# arduino_Uno_Rev3-02-TH-Mod-berred180302.net
KiCad netlist of a schematic drawn in EAGLE
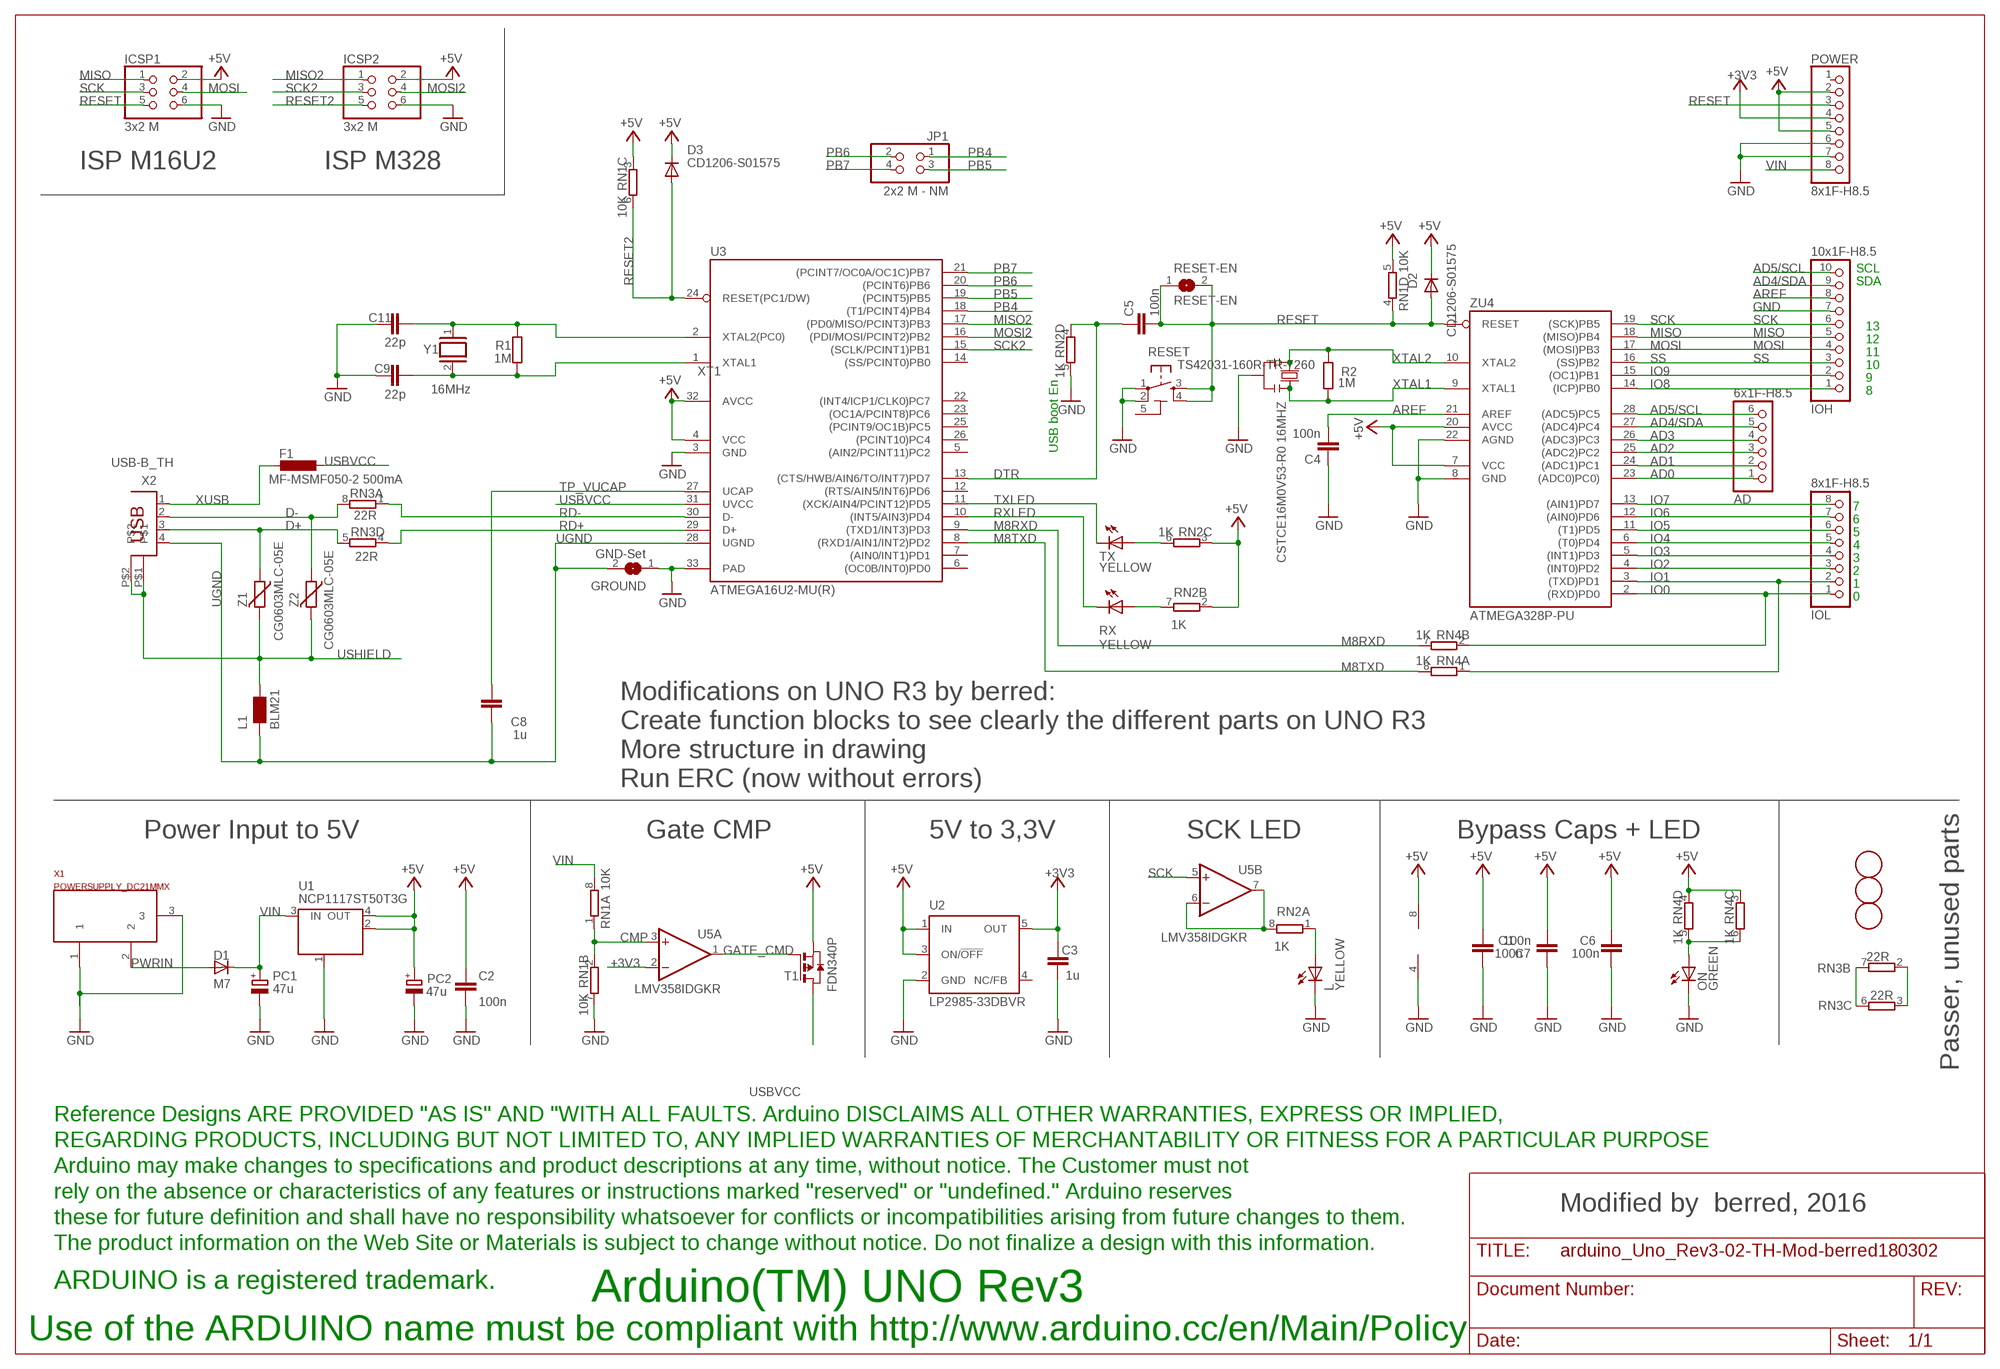
[diagram p0: schematic, sheet 1]

(export (version "E")
  (design (tool "Eeschema 10.0.6"))
  (components
    (comp (ref "AD")
      (value "6x1F-H8.5")
      (footprint "eagle-import:1X06")
      (libsource (lib "eagle-import") (part "PINHD-1X6"))
    )
    (comp (ref "C1")
      (value "100n")
      (footprint "eagle-import:C0603-ROUND")
      (libsource (lib "eagle-import") (part "C-EU0603-RND"))
    )
    (comp (ref "C2")
      (value "100n")
      (footprint "eagle-import:C0603-ROUND")
      (libsource (lib "eagle-import") (part "C-EU0603-RND"))
    )
    (comp (ref "C3")
      (value "1u")
      (footprint "eagle-import:C0603-ROUND")
      (libsource (lib "eagle-import") (part "C-EU0603-RND"))
    )
    (comp (ref "C4")
      (value "100n")
      (footprint "eagle-import:C0603-ROUND")
      (libsource (lib "eagle-import") (part "C-EU0603-RND"))
    )
    (comp (ref "C5")
      (value "100n")
      (footprint "eagle-import:C0603-ROUND")
      (libsource (lib "eagle-import") (part "C-EU0603-RND"))
    )
    (comp (ref "C6")
      (value "100n")
      (footprint "eagle-import:C0603-ROUND")
      (libsource (lib "eagle-import") (part "C-EU0603-RND"))
    )
    (comp (ref "C7")
      (value "100n")
      (footprint "eagle-import:C0603-ROUND")
      (libsource (lib "eagle-import") (part "C-EU0603-RND"))
    )
    (comp (ref "C8")
      (value "1u")
      (footprint "eagle-import:C0603-ROUND")
      (libsource (lib "eagle-import") (part "C-EU0603-RND"))
    )
    (comp (ref "C9")
      (value "22p")
      (footprint "eagle-import:C0603-ROUND")
      (libsource (lib "eagle-import") (part "C-EU0603-RND"))
    )
    (comp (ref "C11")
      (value "22p")
      (footprint "eagle-import:C0603-ROUND")
      (libsource (lib "eagle-import") (part "C-EU0603-RND"))
    )
    (comp (ref "D1")
      (value "M7")
      (footprint "eagle-import:SMB")
      (libsource (lib "eagle-import") (part "DIODE-SMB"))
    )
    (comp (ref "D2")
      (value "CD1206-S01575")
      (footprint "eagle-import:MINIMELF")
      (libsource (lib "eagle-import") (part "DIODE-MINIMELF"))
    )
    (comp (ref "D3")
      (value "CD1206-S01575")
      (footprint "eagle-import:MINIMELF")
      (libsource (lib "eagle-import") (part "DIODE-MINIMELF"))
    )
    (comp (ref "F1")
      (value "MF-MSMF050-2 500mA")
      (footprint "eagle-import:L1812")
      (libsource (lib "eagle-import") (part "L-EUL1812"))
    )
    (comp (ref "FD1")
      (value "FIDUCIALMOUNT")
      (footprint "eagle-import:FIDUCIA-MOUNT")
      (libsource (lib "eagle-import") (part "FIDUCIALMOUNT"))
    )
    (comp (ref "FD2")
      (value "FIDUCIALMOUNT")
      (footprint "eagle-import:FIDUCIA-MOUNT")
      (libsource (lib "eagle-import") (part "FIDUCIALMOUNT"))
    )
    (comp (ref "FD3")
      (value "FIDUCIALMOUNT")
      (footprint "eagle-import:FIDUCIA-MOUNT")
      (libsource (lib "eagle-import") (part "FIDUCIALMOUNT"))
    )
    (comp (ref "GROUND")
      (value "GND-Set")
      (footprint "eagle-import:SJ")
      (libsource (lib "eagle-import") (part "SJ"))
    )
    (comp (ref "ICSP1")
      (value "3x2 M")
      (footprint "eagle-import:2X03")
      (libsource (lib "eagle-import") (part "PINHD-2X3"))
    )
    (comp (ref "ICSP2")
      (value "3x2 M")
      (footprint "eagle-import:2X03")
      (libsource (lib "eagle-import") (part "PINHD-2X3"))
    )
    (comp (ref "IOH")
      (value "10x1F-H8.5")
      (footprint "eagle-import:1X10")
      (libsource (lib "eagle-import") (part "PINHD-1X10_ARD"))
    )
    (comp (ref "IOL")
      (value "8x1F-H8.5")
      (footprint "eagle-import:1X08")
      (libsource (lib "eagle-import") (part "PINHD-1X8"))
    )
    (comp (ref "JP1")
      (value "2x2 M - NM")
      (footprint "eagle-import:2X02")
      (libsource (lib "eagle-import") (part "PINHD-2X2"))
    )
    (comp (ref "L")
      (value "YELLOW")
      (footprint "eagle-import:CHIP-LED0805")
      (libsource (lib "eagle-import") (part "LEDCHIP-LED0805"))
    )
    (comp (ref "L1")
      (value "BLM21")
      (footprint "eagle-import:0805")
      (libsource (lib "eagle-import") (part "WE-CBF_0805"))
    )
    (comp (ref "ON")
      (value "GREEN")
      (footprint "eagle-import:CHIP-LED0805")
      (libsource (lib "eagle-import") (part "LEDCHIP-LED0805"))
    )
    (comp (ref "PC1")
      (value "47u")
      (footprint "eagle-import:PANASONIC_D")
      (libsource (lib "eagle-import") (part "CPOL-EUD"))
    )
    (comp (ref "PC2")
      (value "47u")
      (footprint "eagle-import:PANASONIC_D")
      (libsource (lib "eagle-import") (part "CPOL-EUD"))
    )
    (comp (ref "POWER")
      (value "8x1F-H8.5")
      (footprint "eagle-import:1X08")
      (libsource (lib "eagle-import") (part "PINHD-1X8"))
    )
    (comp (ref "R1")
      (value "1M")
      (footprint "eagle-import:R0603-ROUND")
      (libsource (lib "eagle-import") (part "R-EU_R0603"))
    )
    (comp (ref "R2")
      (value "1M")
      (footprint "eagle-import:R0603-ROUND")
      (libsource (lib "eagle-import") (part "R-EU_R0603"))
    )
    (comp (ref "RESET")
      (value "TS42031-160R-TR-7260")
      (footprint "eagle-import:TS42")
      (libsource (lib "eagle-import") (part "TS42"))
    )
    (comp (ref "RESET-EN")
      (value "RESET-EN")
      (footprint "eagle-import:SJ")
      (libsource (lib "eagle-import") (part "SJ"))
    )
    (comp (ref "RN1")
      (value "10K")
      (footprint "eagle-import:CAY16")
      (libsource (lib "eagle-import") (part "4R-NCAY16"))
    )
    (comp (ref "RN2")
      (value "1K")
      (footprint "eagle-import:CAY16")
      (libsource (lib "eagle-import") (part "4R-NCAY16"))
    )
    (comp (ref "RN3")
      (value "22R")
      (footprint "eagle-import:CAY16")
      (libsource (lib "eagle-import") (part "4R-NCAY16"))
    )
    (comp (ref "RN4")
      (value "1K")
      (footprint "eagle-import:CAY16")
      (libsource (lib "eagle-import") (part "4R-NCAY16"))
    )
    (comp (ref "RX")
      (value "YELLOW")
      (footprint "eagle-import:CHIP-LED0805")
      (libsource (lib "eagle-import") (part "LEDCHIP-LED0805"))
    )
    (comp (ref "T1")
      (value "FDN340P")
      (footprint "eagle-import:SOT-23")
      (libsource (lib "eagle-import") (part "PMOSSOT23"))
    )
    (comp (ref "TX")
      (value "YELLOW")
      (footprint "eagle-import:CHIP-LED0805")
      (libsource (lib "eagle-import") (part "LEDCHIP-LED0805"))
    )
    (comp (ref "U$1")
      (value "DISCLAIMER")
      (footprint "eagle-import:DISCLAIMER")
      (libsource (lib "eagle-import") (part "DISCLAIMER"))
    )
    (comp (ref "U1")
      (value "NCP1117ST50T3G")
      (footprint "eagle-import:SOT223")
      (libsource (lib "eagle-import") (part "MC33269ST-3.3T3"))
    )
    (comp (ref "U2")
      (value "LP2985-33DBVR")
      (footprint "eagle-import:SOT23-DBV")
      (libsource (lib "eagle-import") (part "LP2985-XXDBVR33"))
    )
    (comp (ref "U3")
      (value "ATMEGA16U2-MU(R)")
      (footprint "eagle-import:MLF32")
      (libsource (lib "eagle-import") (part "ATMEGA16U2-MU"))
    )
    (comp (ref "U5")
      (value "LMV358IDGKR")
      (footprint "eagle-import:MSOP08")
      (libsource (lib "eagle-import") (part "LMV358?MMX"))
    )
    (comp (ref "X1")
      (value "POWERSUPPLY_DC21MMX")
      (footprint "eagle-import:POWERSUPPLY_DC-21MM")
      (libsource (lib "eagle-import") (part "POWERSUPPLY_DC21MMX"))
    )
    (comp (ref "X2")
      (value "USB-B_TH")
      (footprint "eagle-import:PN61729")
      (libsource (lib "eagle-import") (part "PN61729"))
    )
    (comp (ref "Y1")
      (value "16MHz")
      (footprint "eagle-import:QS")
      (libsource (lib "eagle-import") (part "XTAL/S"))
    )
    (comp (ref "Y2")
      (value "CSTCE16M0V53-R0 16MHZ")
      (footprint "eagle-import:RESONATOR")
      (libsource (lib "eagle-import") (part "RESONATORMU"))
    )
    (comp (ref "Z1")
      (value "CG0603MLC-05E")
      (footprint "eagle-import:CT_CN0603")
      (libsource (lib "eagle-import") (part "VARISTORCN0603"))
    )
    (comp (ref "Z2")
      (value "CG0603MLC-05E")
      (footprint "eagle-import:CT_CN0603")
      (libsource (lib "eagle-import") (part "VARISTORCN0603"))
    )
    (comp (ref "ZU4")
      (value "ATMEGA328P-PU")
      (footprint "eagle-import:DIL28-3")
      (libsource (lib "eagle-import") (part "ATMEGA328P-PU"))
    )
  )
  (nets
    (net (code "1") (name "+3V3") (class "Default")
      (node (ref "C3") (pin "2") (pinfunction "2_2") (pintype "passive"))
      (node (ref "POWER") (pin "4") (pinfunction "4_4") (pintype "passive"))
      (node (ref "U2") (pin "5") (pinfunction "OUT_5") (pintype "passive"))
      (node (ref "U5") (pin "2") (pinfunction "-IN_2") (pintype "input"))
    )
    (net (code "2") (name "+5V") (class "Default")
      (node (ref "C1") (pin "2") (pinfunction "2_2") (pintype "passive"))
      (node (ref "C2") (pin "2") (pinfunction "2_2") (pintype "passive"))
      (node (ref "C6") (pin "2") (pinfunction "2_2") (pintype "passive"))
      (node (ref "C7") (pin "1") (pinfunction "1_1") (pintype "passive"))
      (node (ref "D2") (pin "C") (pinfunction "C_C") (pintype "passive"))
      (node (ref "D3") (pin "C") (pinfunction "C_C") (pintype "passive"))
      (node (ref "ICSP1") (pin "2") (pinfunction "2_2") (pintype "passive"))
      (node (ref "ICSP2") (pin "2") (pinfunction "2_2") (pintype "passive"))
      (node (ref "PC2") (pin "+") (pinfunction "+_+") (pintype "passive"))
      (node (ref "POWER") (pin "2") (pinfunction "2_2") (pintype "passive"))
      (node (ref "POWER") (pin "5") (pinfunction "5_5") (pintype "passive"))
      (node (ref "RN1") (pin "3") (pinfunction "1_3") (pintype "passive"))
      (node (ref "RN1") (pin "5") (pinfunction "2_5") (pintype "passive"))
      (node (ref "RN2") (pin "2") (pinfunction "1_2") (pintype "passive"))
      (node (ref "RN2") (pin "3") (pinfunction "1_3") (pintype "passive"))
      (node (ref "RN4") (pin "3") (pinfunction "1_3") (pintype "passive"))
      (node (ref "RN4") (pin "4") (pinfunction "1_4") (pintype "passive"))
      (node (ref "T1") (pin "2") (pinfunction "S_2") (pintype "passive"))
      (node (ref "U1") (pin "2") (pinfunction "OUT_2") (pintype "passive"))
      (node (ref "U1") (pin "4") (pinfunction "OUT_4") (pintype "passive"))
      (node (ref "U2") (pin "1") (pinfunction "IN_1") (pintype "input"))
      (node (ref "U2") (pin "3") (pinfunction "ON/~{OFF}_3") (pintype "input"))
      (node (ref "U3") (pin "32") (pinfunction "AVCC_32") (pintype "power_in"))
      (node (ref "U3") (pin "4") (pinfunction "VCC_4") (pintype "power_in"))
      (node (ref "U5") (pin "8") (pinfunction "V+_8") (pintype "power_in"))
      (node (ref "ZU4") (pin "20") (pinfunction "AVCC_20") (pintype "power_in"))
      (node (ref "ZU4") (pin "7") (pinfunction "VCC_7") (pintype "power_in"))
    )
    (net (code "3") (name "/5-GND") (class "Default")
      (node (ref "RESET") (pin "5") (pinfunction "5-GND_5") (pintype "power_in"))
    )
    (net (code "4") (name "/AD0") (class "Default")
      (node (ref "AD") (pin "1") (pinfunction "1_1") (pintype "passive"))
      (node (ref "ZU4") (pin "23") (pinfunction "(ADC0)PC0)_23") (pintype "bidirectional"))
    )
    (net (code "5") (name "/AD1") (class "Default")
      (node (ref "AD") (pin "2") (pinfunction "2_2") (pintype "passive"))
      (node (ref "ZU4") (pin "24") (pinfunction "(ADC1)PC1_24") (pintype "bidirectional"))
    )
    (net (code "6") (name "/AD2") (class "Default")
      (node (ref "AD") (pin "3") (pinfunction "3_3") (pintype "passive"))
      (node (ref "ZU4") (pin "25") (pinfunction "(ADC2)PC2_25") (pintype "bidirectional"))
    )
    (net (code "7") (name "/AD3") (class "Default")
      (node (ref "AD") (pin "4") (pinfunction "4_4") (pintype "passive"))
      (node (ref "ZU4") (pin "26") (pinfunction "(ADC3)PC3_26") (pintype "bidirectional"))
    )
    (net (code "8") (name "/AD4{slash}SDA") (class "Default")
      (node (ref "AD") (pin "5") (pinfunction "5_5") (pintype "passive"))
      (node (ref "IOH") (pin "9") (pinfunction "9_9") (pintype "passive"))
      (node (ref "ZU4") (pin "27") (pinfunction "(ADC4)PC4_27") (pintype "bidirectional"))
    )
    (net (code "9") (name "/AD5{slash}SCL") (class "Default")
      (node (ref "AD") (pin "6") (pinfunction "6_6") (pintype "passive"))
      (node (ref "IOH") (pin "10") (pinfunction "10_10") (pintype "passive"))
      (node (ref "ZU4") (pin "28") (pinfunction "(ADC5)PC5_28") (pintype "bidirectional"))
    )
    (net (code "10") (name "/AREF") (class "Default")
      (node (ref "C4") (pin "2") (pinfunction "2_2") (pintype "passive"))
      (node (ref "IOH") (pin "8") (pinfunction "8_8") (pintype "passive"))
      (node (ref "ZU4") (pin "21") (pinfunction "AREF_21") (pintype "passive"))
    )
    (net (code "11") (name "/CMP") (class "Default")
      (node (ref "RN1") (pin "1") (pinfunction "1_1") (pintype "passive"))
      (node (ref "RN1") (pin "2") (pinfunction "1_2") (pintype "passive"))
      (node (ref "U5") (pin "3") (pinfunction "+IN_3") (pintype "input"))
    )
    (net (code "12") (name "/D+") (class "Default")
      (node (ref "RN3") (pin "5") (pinfunction "2_5") (pintype "passive"))
      (node (ref "X2") (pin "3") (pinfunction "3_3") (pintype "bidirectional"))
      (node (ref "Z1") (pin "1") (pinfunction "1_1") (pintype "passive"))
    )
    (net (code "13") (name "/D-") (class "Default")
      (node (ref "RN3") (pin "8") (pinfunction "2_8") (pintype "passive"))
      (node (ref "X2") (pin "2") (pinfunction "2_2") (pintype "bidirectional"))
      (node (ref "Z2") (pin "1") (pinfunction "1_1") (pintype "passive"))
    )
    (net (code "14") (name "/DTR") (class "Default")
      (node (ref "C5") (pin "1") (pinfunction "1_1") (pintype "passive"))
      (node (ref "RN2") (pin "4") (pinfunction "1_4") (pintype "passive"))
      (node (ref "U3") (pin "13") (pinfunction "(CTS/HWB/AIN6/TO/INT7)PD7_13") (pintype "bidirectional"))
    )
    (net (code "15") (name "/GATE_CMD") (class "Default")
      (node (ref "T1") (pin "3") (pinfunction "G_3") (pintype "passive"))
      (node (ref "U5") (pin "1") (pinfunction "OUT_1") (pintype "output"))
    )
    (net (code "16") (name "/IO0") (class "Default")
      (node (ref "IOL") (pin "1") (pinfunction "1_1") (pintype "passive"))
      (node (ref "RN4") (pin "2") (pinfunction "1_2") (pintype "passive"))
      (node (ref "ZU4") (pin "2") (pinfunction "(RXD)PD0_2") (pintype "bidirectional"))
    )
    (net (code "17") (name "/IO1") (class "Default")
      (node (ref "IOL") (pin "2") (pinfunction "2_2") (pintype "passive"))
      (node (ref "RN4") (pin "1") (pinfunction "1_1") (pintype "passive"))
      (node (ref "ZU4") (pin "3") (pinfunction "(TXD)PD1_3") (pintype "bidirectional"))
    )
    (net (code "18") (name "/IO2") (class "Default")
      (node (ref "IOL") (pin "3") (pinfunction "3_3") (pintype "passive"))
      (node (ref "ZU4") (pin "4") (pinfunction "(INT0)PD2_4") (pintype "bidirectional"))
    )
    (net (code "19") (name "/IO3") (class "Default")
      (node (ref "IOL") (pin "4") (pinfunction "4_4") (pintype "passive"))
      (node (ref "ZU4") (pin "5") (pinfunction "(INT1)PD3_5") (pintype "bidirectional"))
    )
    (net (code "20") (name "/IO4") (class "Default")
      (node (ref "IOL") (pin "5") (pinfunction "5_5") (pintype "passive"))
      (node (ref "ZU4") (pin "6") (pinfunction "(T0)PD4_6") (pintype "bidirectional"))
    )
    (net (code "21") (name "/IO5") (class "Default")
      (node (ref "IOL") (pin "6") (pinfunction "6_6") (pintype "passive"))
      (node (ref "ZU4") (pin "11") (pinfunction "(T1)PD5_11") (pintype "bidirectional"))
    )
    (net (code "22") (name "/IO6") (class "Default")
      (node (ref "IOL") (pin "7") (pinfunction "7_7") (pintype "passive"))
      (node (ref "ZU4") (pin "12") (pinfunction "(AIN0)PD6_12") (pintype "bidirectional"))
    )
    (net (code "23") (name "/IO7") (class "Default")
      (node (ref "IOL") (pin "8") (pinfunction "8_8") (pintype "passive"))
      (node (ref "ZU4") (pin "13") (pinfunction "(AIN1)PD7_13") (pintype "bidirectional"))
    )
    (net (code "24") (name "/IO8") (class "Default")
      (node (ref "IOH") (pin "1") (pinfunction "1_1") (pintype "passive"))
      (node (ref "ZU4") (pin "14") (pinfunction "(ICP)PB0_14") (pintype "bidirectional"))
    )
    (net (code "25") (name "/IO9") (class "Default")
      (node (ref "IOH") (pin "2") (pinfunction "2_2") (pintype "passive"))
      (node (ref "ZU4") (pin "15") (pinfunction "(OC1)PB1_15") (pintype "bidirectional"))
    )
    (net (code "26") (name "/M8RXD") (class "Default")
      (node (ref "RN4") (pin "7") (pinfunction "2_7") (pintype "passive"))
      (node (ref "U3") (pin "9") (pinfunction "(TXD1/INT3)PD3_9") (pintype "bidirectional"))
    )
    (net (code "27") (name "/M8TXD") (class "Default")
      (node (ref "RN4") (pin "8") (pinfunction "2_8") (pintype "passive"))
      (node (ref "U3") (pin "8") (pinfunction "(RXD1/AIN1/INT2)PD2_8") (pintype "bidirectional"))
    )
    (net (code "28") (name "/MISO") (class "Default")
      (node (ref "ICSP1") (pin "1") (pinfunction "1_1") (pintype "passive"))
      (node (ref "IOH") (pin "5") (pinfunction "5_5") (pintype "passive"))
      (node (ref "ZU4") (pin "18") (pinfunction "(MISO)PB4_18") (pintype "bidirectional"))
    )
    (net (code "29") (name "/MISO2") (class "Default")
      (node (ref "ICSP2") (pin "1") (pinfunction "1_1") (pintype "passive"))
      (node (ref "U3") (pin "17") (pinfunction "(PD0/MISO/PCINT3)PB3_17") (pintype "bidirectional"))
    )
    (net (code "30") (name "/MOSI") (class "Default")
      (node (ref "ICSP1") (pin "4") (pinfunction "4_4") (pintype "passive"))
      (node (ref "IOH") (pin "4") (pinfunction "4_4") (pintype "passive"))
      (node (ref "ZU4") (pin "17") (pinfunction "(MOSI)PB3_17") (pintype "bidirectional"))
    )
    (net (code "31") (name "/MOSI2") (class "Default")
      (node (ref "ICSP2") (pin "4") (pinfunction "4_4") (pintype "passive"))
      (node (ref "U3") (pin "16") (pinfunction "(PDI/MOSI/PCINT2)PB2_16") (pintype "bidirectional"))
    )
    (net (code "32") (name "/PB4") (class "Default")
      (node (ref "JP1") (pin "1") (pinfunction "1_1") (pintype "passive"))
      (node (ref "U3") (pin "18") (pinfunction "(T1/PCINT4)PB4_18") (pintype "bidirectional"))
    )
    (net (code "33") (name "/PB5") (class "Default")
      (node (ref "JP1") (pin "3") (pinfunction "3_3") (pintype "passive"))
      (node (ref "U3") (pin "19") (pinfunction "(PCINT5)PB5_19") (pintype "bidirectional"))
    )
    (net (code "34") (name "/PB6") (class "Default")
      (node (ref "JP1") (pin "2") (pinfunction "2_2") (pintype "passive"))
      (node (ref "U3") (pin "20") (pinfunction "(PCINT6)PB6_20") (pintype "bidirectional"))
    )
    (net (code "35") (name "/PB7") (class "Default")
      (node (ref "JP1") (pin "4") (pinfunction "4_4") (pintype "passive"))
      (node (ref "U3") (pin "21") (pinfunction "(PCINT7/OC0A/OC1C)PB7_21") (pintype "bidirectional"))
    )
    (net (code "36") (name "/PWRIN") (class "Default")
      (node (ref "D1") (pin "A") (pinfunction "A_A") (pintype "passive"))
      (node (ref "X1") (pin "2") (pinfunction "2_2") (pintype "power_in"))
    )
    (net (code "37") (name "/RD+") (class "Default")
      (node (ref "RN3") (pin "4") (pinfunction "1_4") (pintype "passive"))
      (node (ref "U3") (pin "29") (pinfunction "D+_29") (pintype "bidirectional"))
    )
    (net (code "38") (name "/RD-") (class "Default")
      (node (ref "RN3") (pin "1") (pinfunction "1_1") (pintype "passive"))
      (node (ref "U3") (pin "30") (pinfunction "D-_30") (pintype "bidirectional"))
    )
    (net (code "39") (name "/RESET") (class "Default")
      (node (ref "C5") (pin "2") (pinfunction "2_2") (pintype "passive"))
      (node (ref "D2") (pin "A") (pinfunction "A_A") (pintype "passive"))
      (node (ref "ICSP1") (pin "5") (pinfunction "5_5") (pintype "passive"))
      (node (ref "POWER") (pin "3") (pinfunction "3_3") (pintype "passive"))
      (node (ref "RESET") (pin "3") (pinfunction "3_3") (pintype "passive"))
      (node (ref "RESET") (pin "4") (pinfunction "4_4") (pintype "passive"))
      (node (ref "RESET-EN") (pin "1") (pinfunction "1_1") (pintype "passive"))
      (node (ref "RESET-EN") (pin "2") (pinfunction "2_2") (pintype "passive"))
      (node (ref "RN1") (pin "4") (pinfunction "1_4") (pintype "passive"))
      (node (ref "ZU4") (pin "1") (pinfunction "RESET_1") (pintype "input"))
    )
    (net (code "40") (name "/RESET2") (class "Default")
      (node (ref "D3") (pin "A") (pinfunction "A_A") (pintype "passive"))
      (node (ref "ICSP2") (pin "5") (pinfunction "5_5") (pintype "passive"))
      (node (ref "RN1") (pin "6") (pinfunction "2_6") (pintype "passive"))
      (node (ref "U3") (pin "24") (pinfunction "RESET(PC1/DW)_24") (pintype "input"))
    )
    (net (code "41") (name "/RXLED") (class "Default")
      (node (ref "RX") (pin "C") (pinfunction "C_C") (pintype "passive"))
      (node (ref "U3") (pin "10") (pinfunction "(INT5/AIN3)PD4_10") (pintype "bidirectional"))
    )
    (net (code "42") (name "/SCK") (class "Default")
      (node (ref "ICSP1") (pin "3") (pinfunction "3_3") (pintype "passive"))
      (node (ref "IOH") (pin "6") (pinfunction "6_6") (pintype "passive"))
      (node (ref "U5") (pin "5") (pinfunction "+IN_5") (pintype "input"))
      (node (ref "ZU4") (pin "19") (pinfunction "(SCK)PB5_19") (pintype "bidirectional"))
    )
    (net (code "43") (name "/SCK2") (class "Default")
      (node (ref "ICSP2") (pin "3") (pinfunction "3_3") (pintype "passive"))
      (node (ref "U3") (pin "15") (pinfunction "(SCLK/PCINT1)PB1_15") (pintype "bidirectional"))
    )
    (net (code "44") (name "/SS") (class "Default")
      (node (ref "IOH") (pin "3") (pinfunction "3_3") (pintype "passive"))
      (node (ref "ZU4") (pin "16") (pinfunction "(SS)PB2_16") (pintype "bidirectional"))
    )
    (net (code "45") (name "/TP_VUCAP") (class "Default")
      (node (ref "C8") (pin "1") (pinfunction "1_1") (pintype "passive"))
      (node (ref "U3") (pin "27") (pinfunction "UCAP_27") (pintype "passive"))
    )
    (net (code "46") (name "/TXLED") (class "Default")
      (node (ref "TX") (pin "C") (pinfunction "C_C") (pintype "passive"))
      (node (ref "U3") (pin "11") (pinfunction "(XCK/AIN4/PCINT12)PD5_11") (pintype "bidirectional"))
    )
    (net (code "47") (name "/UGND") (class "Default")
      (node (ref "C8") (pin "2") (pinfunction "2_2") (pintype "passive"))
      (node (ref "GROUND") (pin "2") (pinfunction "2_2") (pintype "passive"))
      (node (ref "L1") (pin "1") (pinfunction "1_1") (pintype "passive"))
      (node (ref "U3") (pin "28") (pinfunction "UGND_28") (pintype "power_in"))
      (node (ref "X2") (pin "4") (pinfunction "4_4") (pintype "bidirectional"))
    )
    (net (code "48") (name "/USBVCC") (class "Default")
      (node (ref "F1") (pin "1") (pinfunction "1_1") (pintype "passive"))
      (node (ref "T1") (pin "1") (pinfunction "D_1") (pintype "passive"))
      (node (ref "U3") (pin "31") (pinfunction "UVCC_31") (pintype "power_in"))
    )
    (net (code "49") (name "/USHIELD") (class "Default")
      (node (ref "L1") (pin "2") (pinfunction "2_2") (pintype "passive"))
      (node (ref "X2") (pin "P$1") (pinfunction "P$1_P$1") (pintype "bidirectional"))
      (node (ref "X2") (pin "P$2") (pinfunction "P$2_P$2") (pintype "bidirectional"))
      (node (ref "Z1") (pin "2") (pinfunction "2_2") (pintype "passive"))
      (node (ref "Z2") (pin "2") (pinfunction "2_2") (pintype "passive"))
    )
    (net (code "50") (name "/VIN") (class "Default")
      (node (ref "D1") (pin "C") (pinfunction "C_C") (pintype "passive"))
      (node (ref "PC1") (pin "+") (pinfunction "+_+") (pintype "passive"))
      (node (ref "POWER") (pin "8") (pinfunction "8_8") (pintype "passive"))
      (node (ref "RN1") (pin "8") (pinfunction "2_8") (pintype "passive"))
      (node (ref "U1") (pin "3") (pinfunction "IN_3") (pintype "input"))
    )
    (net (code "51") (name "/XT1") (class "Default")
      (node (ref "C9") (pin "1") (pinfunction "1_1") (pintype "passive"))
      (node (ref "R1") (pin "1") (pinfunction "1_1") (pintype "passive"))
      (node (ref "U3") (pin "1") (pinfunction "XTAL1_1") (pintype "bidirectional"))
      (node (ref "Y1") (pin "2") (pinfunction "2_2") (pintype "passive"))
    )
    (net (code "52") (name "/XTAL1") (class "Default")
      (node (ref "R2") (pin "1") (pinfunction "1_1") (pintype "passive"))
      (node (ref "Y2") (pin "3") (pinfunction "3_3") (pintype "passive"))
      (node (ref "ZU4") (pin "9") (pinfunction "XTAL1_9") (pintype "bidirectional"))
    )
    (net (code "53") (name "/XTAL2") (class "Default")
      (node (ref "R2") (pin "2") (pinfunction "2_2") (pintype "passive"))
      (node (ref "Y2") (pin "1") (pinfunction "1_1") (pintype "passive"))
      (node (ref "ZU4") (pin "10") (pinfunction "XTAL2_10") (pintype "bidirectional"))
    )
    (net (code "54") (name "/XUSB") (class "Default")
      (node (ref "F1") (pin "2") (pinfunction "2_2") (pintype "passive"))
      (node (ref "X2") (pin "1") (pinfunction "1_1") (pintype "bidirectional"))
    )
    (net (code "55") (name "GND") (class "Default")
      (node (ref "C1") (pin "1") (pinfunction "1_1") (pintype "passive"))
      (node (ref "C11") (pin "2") (pinfunction "2_2") (pintype "passive"))
      (node (ref "C2") (pin "1") (pinfunction "1_1") (pintype "passive"))
      (node (ref "C3") (pin "1") (pinfunction "1_1") (pintype "passive"))
      (node (ref "C4") (pin "1") (pinfunction "1_1") (pintype "passive"))
      (node (ref "C6") (pin "1") (pinfunction "1_1") (pintype "passive"))
      (node (ref "C7") (pin "2") (pinfunction "2_2") (pintype "passive"))
      (node (ref "C9") (pin "2") (pinfunction "2_2") (pintype "passive"))
      (node (ref "GROUND") (pin "1") (pinfunction "1_1") (pintype "passive"))
      (node (ref "ICSP1") (pin "6") (pinfunction "6_6") (pintype "passive"))
      (node (ref "ICSP2") (pin "6") (pinfunction "6_6") (pintype "passive"))
      (node (ref "IOH") (pin "7") (pinfunction "7_7") (pintype "passive"))
      (node (ref "L") (pin "C") (pinfunction "C_C") (pintype "passive"))
      (node (ref "ON") (pin "C") (pinfunction "C_C") (pintype "passive"))
      (node (ref "PC1") (pin "-") (pinfunction "-_-") (pintype "passive"))
      (node (ref "PC2") (pin "-") (pinfunction "-_-") (pintype "passive"))
      (node (ref "POWER") (pin "6") (pinfunction "6_6") (pintype "passive"))
      (node (ref "POWER") (pin "7") (pinfunction "7_7") (pintype "passive"))
      (node (ref "RESET") (pin "1") (pinfunction "1_1") (pintype "passive"))
      (node (ref "RESET") (pin "2") (pinfunction "2_2") (pintype "passive"))
      (node (ref "RN1") (pin "7") (pinfunction "2_7") (pintype "passive"))
      (node (ref "RN2") (pin "5") (pinfunction "2_5") (pintype "passive"))
      (node (ref "U1") (pin "1") (pinfunction "GND/ADJ_1") (pintype "input"))
      (node (ref "U2") (pin "2") (pinfunction "GND_2") (pintype "power_in"))
      (node (ref "U3") (pin "3") (pinfunction "GND_3") (pintype "power_in"))
      (node (ref "U3") (pin "33") (pinfunction "PAD_33") (pintype "power_in"))
      (node (ref "U5") (pin "4") (pinfunction "V-_4") (pintype "power_in"))
      (node (ref "X1") (pin "1") (pinfunction "1_1") (pintype "power_in"))
      (node (ref "X1") (pin "3") (pinfunction "3_3") (pintype "power_in"))
      (node (ref "Y2") (pin "2") (pinfunction "2_2") (pintype "passive"))
      (node (ref "ZU4") (pin "22") (pinfunction "AGND_22") (pintype "power_in"))
      (node (ref "ZU4") (pin "8") (pinfunction "GND_8") (pintype "power_in"))
    )
    (net (code "56") (name "Net-(L-PadA)") (class "Default")
      (node (ref "L") (pin "A") (pinfunction "A_A") (pintype "passive"))
      (node (ref "RN2") (pin "1") (pinfunction "1_1") (pintype "passive"))
    )
    (net (code "57") (name "Net-(RN2A-2)") (class "Default")
      (node (ref "RN2") (pin "8") (pinfunction "2_8") (pintype "passive"))
      (node (ref "U5") (pin "6") (pinfunction "-IN_6") (pintype "input"))
      (node (ref "U5") (pin "7") (pinfunction "OUT_7") (pintype "output"))
    )
    (net (code "58") (name "Net-(RN2B-2)") (class "Default")
      (node (ref "RN2") (pin "7") (pinfunction "2_7") (pintype "passive"))
      (node (ref "RX") (pin "A") (pinfunction "A_A") (pintype "passive"))
    )
    (net (code "59") (name "Net-(RN2C-2)") (class "Default")
      (node (ref "RN2") (pin "6") (pinfunction "2_6") (pintype "passive"))
      (node (ref "TX") (pin "A") (pinfunction "A_A") (pintype "passive"))
    )
    (net (code "60") (name "Net-(RN3B-1)") (class "Default")
      (node (ref "RN3") (pin "2") (pinfunction "1_2") (pintype "passive"))
      (node (ref "RN3") (pin "3") (pinfunction "1_3") (pintype "passive"))
    )
    (net (code "61") (name "Net-(RN3B-2)") (class "Default")
      (node (ref "RN3") (pin "6") (pinfunction "2_6") (pintype "passive"))
      (node (ref "RN3") (pin "7") (pinfunction "2_7") (pintype "passive"))
    )
    (net (code "62") (name "Net-(RN4C-2)") (class "Default")
      (node (ref "ON") (pin "A") (pinfunction "A_A") (pintype "passive"))
      (node (ref "RN4") (pin "5") (pinfunction "2_5") (pintype "passive"))
      (node (ref "RN4") (pin "6") (pinfunction "2_6") (pintype "passive"))
    )
    (net (code "63") (name "Net-(U3-XTAL2(PC0))") (class "Default")
      (node (ref "C11") (pin "1") (pinfunction "1_1") (pintype "passive"))
      (node (ref "R1") (pin "2") (pinfunction "2_2") (pintype "passive"))
      (node (ref "U3") (pin "2") (pinfunction "XTAL2(PC0)_2") (pintype "bidirectional"))
      (node (ref "Y1") (pin "1") (pinfunction "1_1") (pintype "passive"))
    )
    (net (code "64") (name "unconnected-(POWER-Pad1)") (class "Default")
      (node (ref "POWER") (pin "1") (pinfunction "1_1") (pintype "passive"))
    )
    (net (code "65") (name "unconnected-(U2-NC{slash}FB-Pad4)") (class "Default")
      (node (ref "U2") (pin "4") (pinfunction "NC/FB_4") (pintype "passive"))
    )
    (net (code "66") (name "unconnected-(U3-(AIN0{slash}INT1)PD1-Pad7)") (class "Default")
      (node (ref "U3") (pin "7") (pinfunction "(AIN0/INT1)PD1_7") (pintype "bidirectional"))
    )
    (net (code "67") (name "unconnected-(U3-(AIN2{slash}PCINT11)PC2-Pad5)") (class "Default")
      (node (ref "U3") (pin "5") (pinfunction "(AIN2/PCINT11)PC2_5") (pintype "bidirectional"))
    )
    (net (code "68") (name "unconnected-(U3-(INT4{slash}ICP1{slash}CLK0)PC7-Pad22)") (class "Default")
      (node (ref "U3") (pin "22") (pinfunction "(INT4/ICP1/CLK0)PC7_22") (pintype "bidirectional"))
    )
    (net (code "69") (name "unconnected-(U3-(OC0B{slash}INT0)PD0-Pad6)") (class "Default")
      (node (ref "U3") (pin "6") (pinfunction "(OC0B/INT0)PD0_6") (pintype "bidirectional"))
    )
    (net (code "70") (name "unconnected-(U3-(OC1A{slash}PCINT8)PC6-Pad23)") (class "Default")
      (node (ref "U3") (pin "23") (pinfunction "(OC1A/PCINT8)PC6_23") (pintype "bidirectional"))
    )
    (net (code "71") (name "unconnected-(U3-(PCINT9{slash}OC1B)PC5-Pad25)") (class "Default")
      (node (ref "U3") (pin "25") (pinfunction "(PCINT9/OC1B)PC5_25") (pintype "bidirectional"))
    )
    (net (code "72") (name "unconnected-(U3-(PCINT10)PC4-Pad26)") (class "Default")
      (node (ref "U3") (pin "26") (pinfunction "(PCINT10)PC4_26") (pintype "bidirectional"))
    )
    (net (code "73") (name "unconnected-(U3-(RTS{slash}AIN5{slash}INT6)PD6-Pad12)") (class "Default")
      (node (ref "U3") (pin "12") (pinfunction "(RTS/AIN5/INT6)PD6_12") (pintype "bidirectional"))
    )
    (net (code "74") (name "unconnected-(U3-(SS{slash}PCINT0)PB0-Pad14)") (class "Default")
      (node (ref "U3") (pin "14") (pinfunction "(SS/PCINT0)PB0_14") (pintype "bidirectional"))
    )
  )
)
